# MCU.net
KiCad netlist of a schematic drawn in Altium Designer
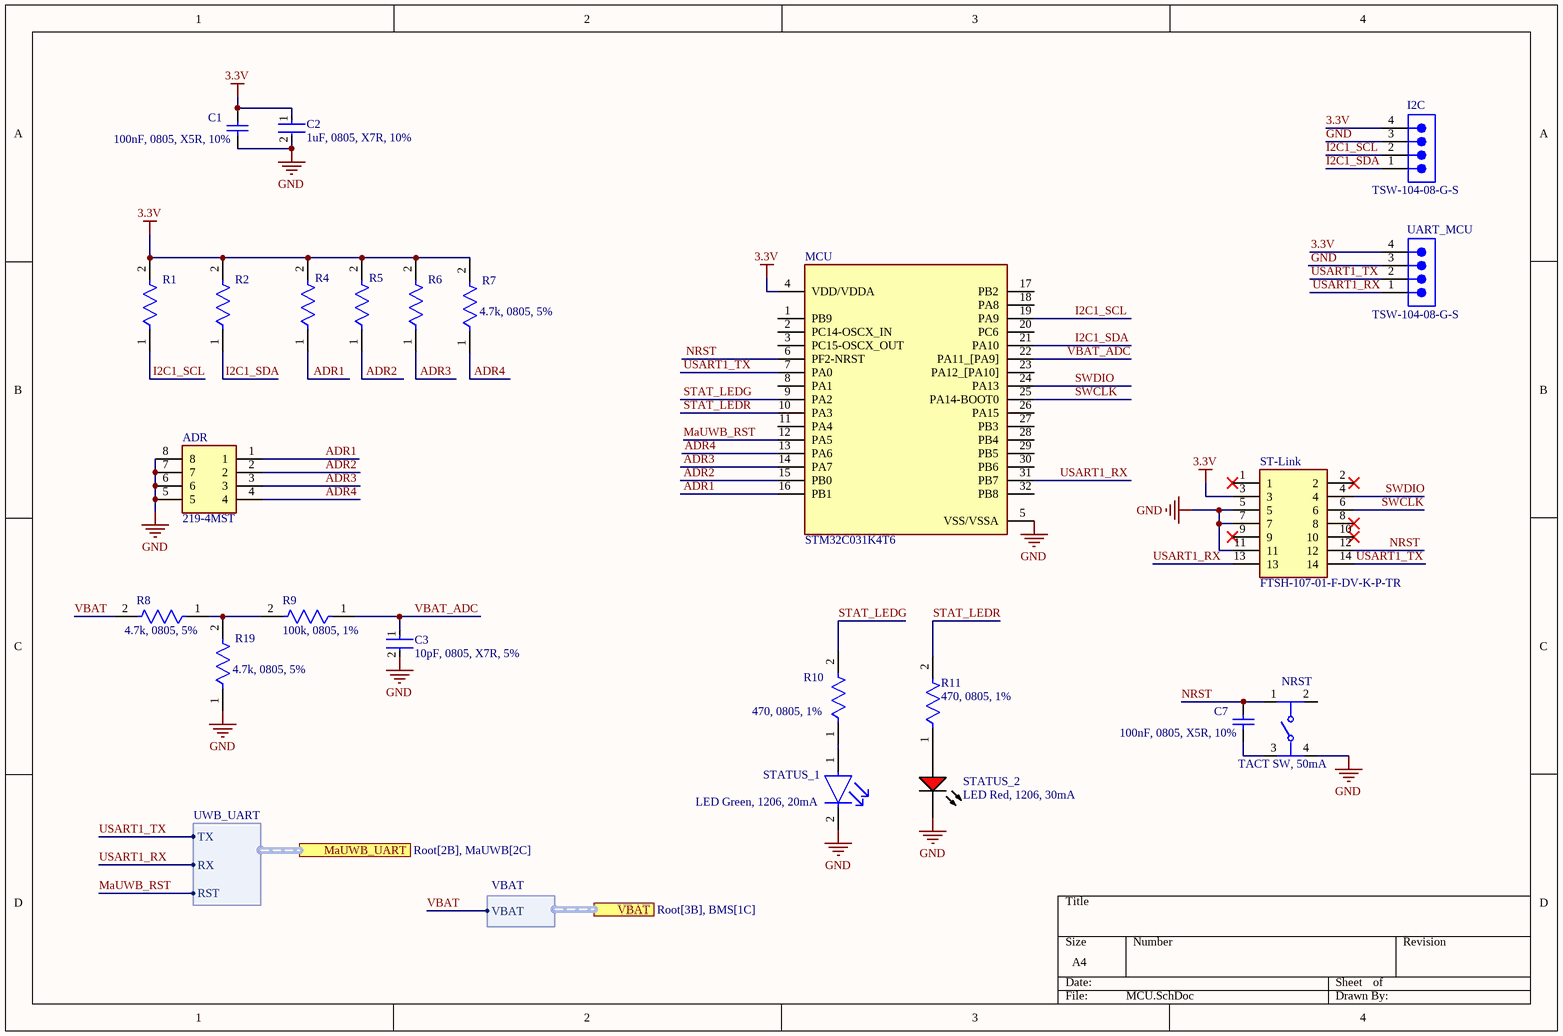
[diagram p0: MCU.SchDoc]

(export (version "E")
  (design (tool "Eeschema 10.0.6"))
  (components
    (comp (ref "ADR")
      (value "219-4MST")
      (footprint "SamacSys:2194MST")
      (description "Switch")
      (fields (field (name "MOUSER PART NUMBER") "774-2194MST"))
      (libsource (lib "*") (part "219-4MST"))
    )
    (comp (ref "C1")
      (value "100nF, 0805, X5R, 10%")
      (footprint "CAPC2013X140X50ML20T25")
      (fields
        (field (name "PART NUMBER") "08055D104KAT2A")
        (field (name "MANUFACTURER") "AVX Interconnect / Elco")
      )
      (libsource (lib "Altium Content Vault") (part "CAP"))
    )
    (comp (ref "C2")
      (value "1uF, 0805, X7R, 10%")
      (footprint "FP-CC0805-0_85-MFG")
      (description "CC0805 1 uF X7R 10.00% 50 V")
      (fields
        (field (name "MANUFACTURER PART NUMBER") "CC0805KFX7R9BB105")
        (field (name "OCTOPART") "https://octopart.com/cc0805kfx7r9bb105-yageo-76378930")
      )
      (libsource (lib "Altium Content Vault") (part "11868f565c42a9108669ba33697ecf6"))
    )
    (comp (ref "C3")
      (value "10pF, 0805, X7R, 5%")
      (footprint "FP-C0805C-DN-MFG")
      (description "C0805 10 pF X7R 30ppm/°C 5.00% 50 V")
      (fields
        (field (name "OCTOPART") "https://octopart.com/c0805c100j5ractu-kemet-81794931")
        (field (name "MANUFACTURER PART NUMBER") "C0805C100J5RACTU")
      )
      (libsource (lib "Altium Content Vault") (part "b4654b650e69147ec39a6b967a45e02"))
    )
    (comp (ref "C7")
      (value "100nF, 0805, X5R, 10%")
      (footprint "CAPC2013X140X50ML20T25")
      (fields
        (field (name "PART NUMBER") "08055D104KAT2A")
        (field (name "MANUFACTURER") "AVX Interconnect / Elco")
      )
      (libsource (lib "Altium Content Vault") (part "CAP"))
    )
    (comp (ref "I2C")
      (value "TSW-104-08-G-S")
      (footprint "SMTC-TSW-104-08-X-S")
      (description "0.025\" SQ Post Header, Through-hole, Vertical, -55 to 125 degC, 2.54 mm Pitch, 4-Pin, Male, RoHS")
      (fields (field (name "MANUFACTURER") "Samtec"))
      (libsource (lib "Altium Content Vault") (part "SMTC-TSW-104-08-X-S"))
    )
    (comp (ref "MCU")
      (value "STM32C031K4T6")
      (footprint "SamacSys:QFP80P900X900X160-32N")
      (description "Integrated Circuit")
      (fields (field (name "MOUSER PART NUMBER") "511-STM32C031K4T6"))
      (libsource (lib "SamacSys") (part "STM32C031K4T6"))
    )
    (comp (ref "NRST")
      (value "TACT SW, 50mA")
      (footprint "FP-PTS647SK38SMTR2LFS-MFG")
      (description "TACT 4.5 X 4.5, 3.8 MM H, 2.5N,")
      (libsource (lib "Altium Content Vault") (part "1adf0dd01260c80cf25a44bfd6b99ba"))
    )
    (comp (ref "R1")
      (value "~")
      (footprint "FP-RMCF0805-MFG")
      (description "4.7kΩ ±5% 0.125W 0805 Thick Film Chip Resistor AEC-Q200 compliant")
      (fields (field (name "TOLERANCE") "5%"))
      (libsource (lib "Altium Content Vault") (part "1029c3af85768c4190bb7ad29bc67b5"))
    )
    (comp (ref "R2")
      (value "~")
      (footprint "FP-RMCF0805-MFG")
      (description "4.7kΩ ±5% 0.125W 0805 Thick Film Chip Resistor AEC-Q200 compliant")
      (fields (field (name "TOLERANCE") "5%"))
      (libsource (lib "Altium Content Vault") (part "1029c3af85768c4190bb7ad29bc67b5"))
    )
    (comp (ref "R4")
      (value "~")
      (footprint "FP-RMCF0805-MFG")
      (description "4.7kΩ ±5% 0.125W 0805 Thick Film Chip Resistor AEC-Q200 compliant")
      (fields (field (name "TOLERANCE") "5%"))
      (libsource (lib "Altium Content Vault") (part "1029c3af85768c4190bb7ad29bc67b5"))
    )
    (comp (ref "R5")
      (value "~")
      (footprint "FP-RMCF0805-MFG")
      (description "4.7kΩ ±5% 0.125W 0805 Thick Film Chip Resistor AEC-Q200 compliant")
      (fields (field (name "TOLERANCE") "5%"))
      (libsource (lib "Altium Content Vault") (part "1029c3af85768c4190bb7ad29bc67b5"))
    )
    (comp (ref "R6")
      (value "~")
      (footprint "FP-RMCF0805-MFG")
      (description "4.7kΩ ±5% 0.125W 0805 Thick Film Chip Resistor AEC-Q200 compliant")
      (fields (field (name "TOLERANCE") "5%"))
      (libsource (lib "Altium Content Vault") (part "1029c3af85768c4190bb7ad29bc67b5"))
    )
    (comp (ref "R7")
      (value "4.7k, 0805, 5%")
      (footprint "FP-RMCF0805-MFG")
      (description "4.7kΩ ±5% 0.125W 0805 Thick Film Chip Resistor AEC-Q200 compliant")
      (fields (field (name "TOLERANCE") "5%"))
      (libsource (lib "Altium Content Vault") (part "1029c3af85768c4190bb7ad29bc67b5"))
    )
    (comp (ref "R8")
      (value "4.7k, 0805, 5%")
      (footprint "FP-RMCF0805-MFG")
      (description "4.7kΩ ±5% 0.125W 0805 Thick Film Chip Resistor AEC-Q200 compliant")
      (fields (field (name "TOLERANCE") "5%"))
      (libsource (lib "Altium Content Vault") (part "1029c3af85768c4190bb7ad29bc67b5"))
    )
    (comp (ref "R9")
      (value "100k, 0805, 1%")
      (footprint "FP-CRGCQ0805-IPC_C")
      (description "CRGCQ 0805 100K 1%")
      (fields
        (field (name "MANUFACTURER") "TE Connectivity")
        (field (name "OCTOPART") "https://octopart.com/crgcq0805f100k-te+connectivity-91018138")
      )
      (libsource (lib "Altium Content Vault") (part "1029c3af85768c4190bb7ad29bc67b5"))
    )
    (comp (ref "R10")
      (value "470, 0805, 1%")
      (footprint "FP-RMCF0805-IPC_C")
      (description "470Ω ±1% 0.125W 0805 Thick Film Chip Resistor AEC-Q200 compliant")
      (fields (field (name "TOLERANCE") "1%"))
      (libsource (lib "Altium Content Vault") (part "1029c3af85768c4190bb7ad29bc67b5"))
    )
    (comp (ref "R11")
      (value "470, 0805, 1%")
      (footprint "FP-RMCF0805-IPC_C")
      (description "470Ω ±1% 0.125W 0805 Thick Film Chip Resistor AEC-Q200 compliant")
      (fields (field (name "TOLERANCE") "1%"))
      (libsource (lib "Altium Content Vault") (part "1029c3af85768c4190bb7ad29bc67b5"))
    )
    (comp (ref "R19")
      (value "4.7k, 0805, 5%")
      (footprint "FP-RMCF0805-MFG")
      (description "4.7kΩ ±5% 0.125W 0805 Thick Film Chip Resistor AEC-Q200 compliant")
      (fields (field (name "TOLERANCE") "5%"))
      (libsource (lib "Altium Content Vault") (part "1029c3af85768c4190bb7ad29bc67b5"))
    )
    (comp (ref "ST-Link")
      (value "FTSH-107-01-F-DV-K-P-TR")
      (footprint "SamacSys:FTSH-107-XX-YYY-DV-K-P-TR")
      (description "Connector")
      (fields (field (name "MOUSER PART NUMBER") "200-FTSH10701FDVKPTR"))
      (libsource (lib "*") (part "FTSH-107-01-F-DV-K-P-TR"))
    )
    (comp (ref "STATUS_1")
      (value "LED Green, 1206, 20mA")
      (footprint "FP-SML-LX1206GC-TR-MFG")
      (description "LED GREEN CLEAR 1206 SMD")
      (libsource (lib "Altium Content Vault") (part "ab1c01a81903e929fc6c44469aada92"))
    )
    (comp (ref "STATUS_2")
      (value "LED Red, 1206, 30mA")
      (footprint "LUMX-SML-LX1206IC_V")
      (description "LED Red, 65 mW, -40 to 85 degC, 2-Pin SMD, RoHS, Tape and Reel")
      (fields (field (name "MANUFACTURER") "Lumex") (field (name "PART NO") "SML-LX1206IC-TR"))
      (libsource (lib "Altium Content Vault") (part "LED-RED-AK-2"))
    )
    (comp (ref "UART_MCU")
      (value "TSW-104-08-G-S")
      (footprint "SMTC-TSW-104-08-X-S")
      (description "0.025\" SQ Post Header, Through-hole, Vertical, -55 to 125 degC, 2.54 mm Pitch, 4-Pin, Male, RoHS")
      (fields (field (name "MANUFACTURER") "Samtec"))
      (libsource (lib "Altium Content Vault") (part "SMTC-TSW-104-08-X-S"))
    )
  )
  (nets
    (net (code "2") (name "/ADR1") (class "Default")
      (node (ref "ADR") (pin "1") (pinfunction "1_1") (pintype "passive"))
      (node (ref "MCU") (pin "16") (pinfunction "PB1_16") (pintype "passive"))
      (node (ref "R4") (pin "1") (pinfunction "1_1") (pintype "passive"))
    )
    (net (code "3") (name "/ADR2") (class "Default")
      (node (ref "ADR") (pin "2") (pinfunction "2_2") (pintype "passive"))
      (node (ref "MCU") (pin "15") (pinfunction "PB0_15") (pintype "passive"))
      (node (ref "R5") (pin "1") (pinfunction "1_1") (pintype "passive"))
    )
    (net (code "4") (name "/ADR3") (class "Default")
      (node (ref "ADR") (pin "3") (pinfunction "3_3") (pintype "passive"))
      (node (ref "MCU") (pin "14") (pinfunction "PA7_14") (pintype "passive"))
      (node (ref "R6") (pin "1") (pinfunction "1_1") (pintype "passive"))
    )
    (net (code "5") (name "/ADR4") (class "Default")
      (node (ref "ADR") (pin "4") (pinfunction "4_4") (pintype "passive"))
      (node (ref "MCU") (pin "13") (pinfunction "PA6_13") (pintype "passive"))
      (node (ref "R7") (pin "1") (pinfunction "1_1") (pintype "passive"))
    )
    (net (code "6") (name "/I2C1_SCL") (class "Default")
      (node (ref "I2C") (pin "2") (pinfunction "2_2") (pintype "passive"))
      (node (ref "MCU") (pin "19") (pinfunction "PA9_19") (pintype "passive"))
      (node (ref "R1") (pin "1") (pinfunction "1_1") (pintype "passive"))
    )
    (net (code "7") (name "/I2C1_SDA") (class "Default")
      (node (ref "I2C") (pin "1") (pinfunction "1_1") (pintype "passive"))
      (node (ref "MCU") (pin "21") (pinfunction "PA10_21") (pintype "passive"))
      (node (ref "R2") (pin "1") (pinfunction "1_1") (pintype "passive"))
    )
    (net (code "8") (name "/MaUWB_RST") (class "Default")
      (node (ref "MCU") (pin "12") (pinfunction "PA5_12") (pintype "passive"))
    )
    (net (code "9") (name "/NRST") (class "Default")
      (node (ref "C7") (pin "2") (pinfunction "2_2") (pintype "passive"))
      (node (ref "MCU") (pin "6") (pinfunction "PF2-NRST_6") (pintype "passive"))
      (node (ref "NRST") (pin "1") (pinfunction "1_1") (pintype "passive"))
      (node (ref "ST-Link") (pin "12") (pinfunction "12_12") (pintype "passive"))
    )
    (net (code "10") (name "/STAT_LEDG") (class "Default")
      (node (ref "MCU") (pin "9") (pinfunction "PA2_9") (pintype "passive"))
      (node (ref "R10") (pin "2") (pinfunction "2_2") (pintype "passive"))
    )
    (net (code "11") (name "/STAT_LEDR") (class "Default")
      (node (ref "MCU") (pin "10") (pinfunction "PA3_10") (pintype "passive"))
      (node (ref "R11") (pin "2") (pinfunction "2_2") (pintype "passive"))
    )
    (net (code "12") (name "/SWCLK") (class "Default")
      (node (ref "MCU") (pin "25") (pinfunction "PA14-BOOT0_25") (pintype "passive"))
      (node (ref "ST-Link") (pin "6") (pinfunction "6_6") (pintype "passive"))
    )
    (net (code "13") (name "/SWDIO") (class "Default")
      (node (ref "MCU") (pin "24") (pinfunction "PA13_24") (pintype "passive"))
      (node (ref "ST-Link") (pin "4") (pinfunction "4_4") (pintype "passive"))
    )
    (net (code "14") (name "/USART1_RX") (class "Default")
      (node (ref "MCU") (pin "31") (pinfunction "PB7_31") (pintype "passive"))
      (node (ref "ST-Link") (pin "13") (pinfunction "13_13") (pintype "passive"))
      (node (ref "UART_MCU") (pin "1") (pinfunction "1_1") (pintype "passive"))
    )
    (net (code "15") (name "/USART1_TX") (class "Default")
      (node (ref "MCU") (pin "7") (pinfunction "PA0_7") (pintype "passive"))
      (node (ref "ST-Link") (pin "14") (pinfunction "14_14") (pintype "passive"))
      (node (ref "UART_MCU") (pin "2") (pinfunction "2_2") (pintype "passive"))
    )
    (net (code "16") (name "/VBAT") (class "Default")
      (node (ref "R8") (pin "2") (pinfunction "2_2") (pintype "passive"))
    )
    (net (code "17") (name "/VBAT_ADC") (class "Default")
      (node (ref "C3") (pin "1") (pinfunction "1_1") (pintype "passive"))
      (node (ref "MCU") (pin "22") (pinfunction "PA11_[PA9]_22") (pintype "passive"))
      (node (ref "R9") (pin "1") (pinfunction "1_1") (pintype "passive"))
    )
    (net (code "20") (name "3.3V") (class "Default")
      (node (ref "C1") (pin "2") (pinfunction "2_2") (pintype "passive"))
      (node (ref "C2") (pin "1") (pinfunction "1_1") (pintype "passive"))
      (node (ref "I2C") (pin "4") (pinfunction "4_4") (pintype "passive"))
      (node (ref "MCU") (pin "4") (pinfunction "VDD/VDDA_4") (pintype "passive"))
      (node (ref "R1") (pin "2") (pinfunction "2_2") (pintype "passive"))
      (node (ref "R2") (pin "2") (pinfunction "2_2") (pintype "passive"))
      (node (ref "R4") (pin "2") (pinfunction "2_2") (pintype "passive"))
      (node (ref "R5") (pin "2") (pinfunction "2_2") (pintype "passive"))
      (node (ref "R6") (pin "2") (pinfunction "2_2") (pintype "passive"))
      (node (ref "R7") (pin "2") (pinfunction "2_2") (pintype "passive"))
      (node (ref "ST-Link") (pin "3") (pinfunction "3_3") (pintype "passive"))
      (node (ref "UART_MCU") (pin "4") (pinfunction "4_4") (pintype "passive"))
    )
    (net (code "21") (name "GND") (class "Default")
      (node (ref "ADR") (pin "5") (pinfunction "5_5") (pintype "passive"))
      (node (ref "ADR") (pin "6") (pinfunction "6_6") (pintype "passive"))
      (node (ref "ADR") (pin "7") (pinfunction "7_7") (pintype "passive"))
      (node (ref "ADR") (pin "8") (pinfunction "8_8") (pintype "passive"))
      (node (ref "C1") (pin "1") (pinfunction "1_1") (pintype "passive"))
      (node (ref "C2") (pin "2") (pinfunction "2_2") (pintype "passive"))
      (node (ref "C3") (pin "2") (pinfunction "2_2") (pintype "passive"))
      (node (ref "I2C") (pin "3") (pinfunction "3_3") (pintype "passive"))
      (node (ref "MCU") (pin "5") (pinfunction "VSS/VSSA_5") (pintype "passive"))
      (node (ref "NRST") (pin "4") (pinfunction "4_4") (pintype "passive"))
      (node (ref "R19") (pin "1") (pinfunction "1_1") (pintype "passive"))
      (node (ref "ST-Link") (pin "11") (pinfunction "11_11") (pintype "passive"))
      (node (ref "ST-Link") (pin "5") (pinfunction "5_5") (pintype "passive"))
      (node (ref "ST-Link") (pin "7") (pinfunction "7_7") (pintype "passive"))
      (node (ref "STATUS_1") (pin "2") (pinfunction "C_2") (pintype "passive"))
      (node (ref "STATUS_2") (pin "2") (pinfunction "K_2") (pintype "passive"))
      (node (ref "UART_MCU") (pin "3") (pinfunction "3_3") (pintype "passive"))
    )
    (net (code "22") (name "Net-(C7-Pad1)") (class "Default")
      (node (ref "C7") (pin "1") (pinfunction "1_1") (pintype "passive"))
      (node (ref "NRST") (pin "3") (pinfunction "3_3") (pintype "passive"))
    )
    (net (code "23") (name "Net-(R19-Pad2)") (class "Default")
      (node (ref "R19") (pin "2") (pinfunction "2_2") (pintype "passive"))
      (node (ref "R8") (pin "1") (pinfunction "1_1") (pintype "passive"))
      (node (ref "R9") (pin "2") (pinfunction "2_2") (pintype "passive"))
    )
    (net (code "24") (name "Net-(STATUS_1-A)") (class "Default")
      (node (ref "R10") (pin "1") (pinfunction "1_1") (pintype "passive"))
      (node (ref "STATUS_1") (pin "1") (pinfunction "A_1") (pintype "passive"))
    )
    (net (code "25") (name "Net-(STATUS_2-A)") (class "Default")
      (node (ref "R11") (pin "1") (pinfunction "1_1") (pintype "passive"))
      (node (ref "STATUS_2") (pin "1") (pinfunction "A_1") (pintype "passive"))
    )
    (net (code "26") (name "unconnected-(MCU-PA1-Pad8)") (class "Default")
      (node (ref "MCU") (pin "8") (pinfunction "PA1_8") (pintype "passive"))
    )
    (net (code "27") (name "unconnected-(MCU-PA4-Pad11)") (class "Default")
      (node (ref "MCU") (pin "11") (pinfunction "PA4_11") (pintype "passive"))
    )
    (net (code "28") (name "unconnected-(MCU-PA8-Pad18)") (class "Default")
      (node (ref "MCU") (pin "18") (pinfunction "PA8_18") (pintype "passive"))
    )
    (net (code "29") (name "unconnected-(MCU-PA12_[PA10]-Pad23)") (class "Default")
      (node (ref "MCU") (pin "23") (pinfunction "PA12_[PA10]_23") (pintype "passive"))
    )
    (net (code "30") (name "unconnected-(MCU-PA15-Pad26)") (class "Default")
      (node (ref "MCU") (pin "26") (pinfunction "PA15_26") (pintype "passive"))
    )
    (net (code "31") (name "unconnected-(MCU-PB2-Pad17)") (class "Default")
      (node (ref "MCU") (pin "17") (pinfunction "PB2_17") (pintype "passive"))
    )
    (net (code "32") (name "unconnected-(MCU-PB3-Pad27)") (class "Default")
      (node (ref "MCU") (pin "27") (pinfunction "PB3_27") (pintype "passive"))
    )
    (net (code "33") (name "unconnected-(MCU-PB4-Pad28)") (class "Default")
      (node (ref "MCU") (pin "28") (pinfunction "PB4_28") (pintype "passive"))
    )
    (net (code "34") (name "unconnected-(MCU-PB5-Pad29)") (class "Default")
      (node (ref "MCU") (pin "29") (pinfunction "PB5_29") (pintype "passive"))
    )
    (net (code "35") (name "unconnected-(MCU-PB6-Pad30)") (class "Default")
      (node (ref "MCU") (pin "30") (pinfunction "PB6_30") (pintype "passive"))
    )
    (net (code "36") (name "unconnected-(MCU-PB8-Pad32)") (class "Default")
      (node (ref "MCU") (pin "32") (pinfunction "PB8_32") (pintype "passive"))
    )
    (net (code "37") (name "unconnected-(MCU-PB9-Pad1)") (class "Default")
      (node (ref "MCU") (pin "1") (pinfunction "PB9_1") (pintype "passive"))
    )
    (net (code "38") (name "unconnected-(MCU-PC6-Pad20)") (class "Default")
      (node (ref "MCU") (pin "20") (pinfunction "PC6_20") (pintype "passive"))
    )
    (net (code "39") (name "unconnected-(MCU-PC14-OSCX_IN-Pad2)") (class "Default")
      (node (ref "MCU") (pin "2") (pinfunction "PC14-OSCX_IN_2") (pintype "passive"))
    )
    (net (code "40") (name "unconnected-(MCU-PC15-OSCX_OUT-Pad3)") (class "Default")
      (node (ref "MCU") (pin "3") (pinfunction "PC15-OSCX_OUT_3") (pintype "passive"))
    )
    (net (code "41") (name "unconnected-(NRST-Pad2)") (class "Default")
      (node (ref "NRST") (pin "2") (pinfunction "2_2") (pintype "passive"))
    )
    (net (code "42") (name "unconnected-(ST-Link-Pad1)") (class "Default")
      (node (ref "ST-Link") (pin "1") (pinfunction "1_1") (pintype "passive+no_connect"))
    )
    (net (code "43") (name "unconnected-(ST-Link-Pad2)") (class "Default")
      (node (ref "ST-Link") (pin "2") (pinfunction "2_2") (pintype "passive+no_connect"))
    )
    (net (code "44") (name "unconnected-(ST-Link-Pad8)") (class "Default")
      (node (ref "ST-Link") (pin "8") (pinfunction "8_8") (pintype "passive+no_connect"))
    )
    (net (code "45") (name "unconnected-(ST-Link-Pad9)") (class "Default")
      (node (ref "ST-Link") (pin "9") (pinfunction "9_9") (pintype "passive+no_connect"))
    )
    (net (code "46") (name "unconnected-(ST-Link-Pad10)") (class "Default")
      (node (ref "ST-Link") (pin "10") (pinfunction "10_10") (pintype "passive+no_connect"))
    )
  )
)
